# OUTPUT_HEADERS.net
KiCad netlist of a schematic drawn in Altium Designer
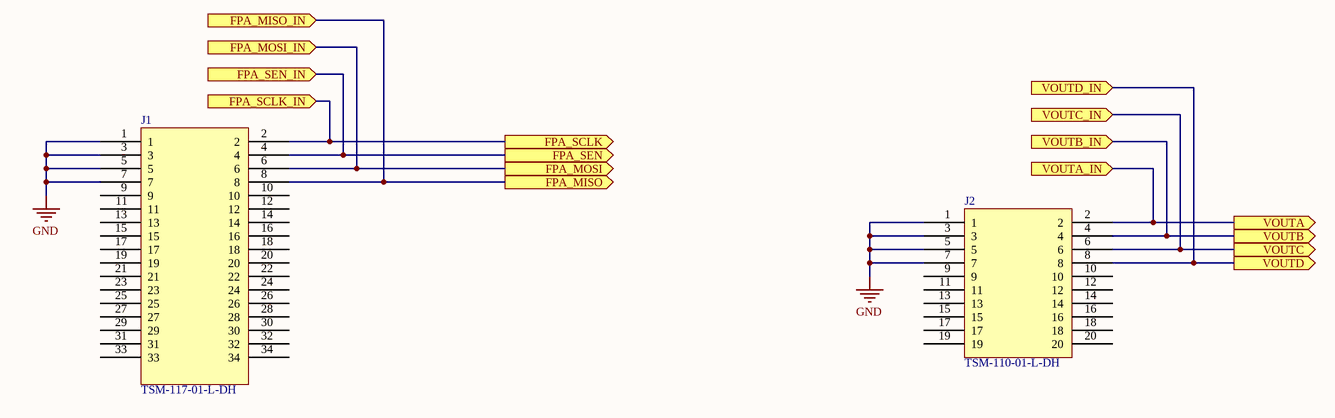
[diagram p0: OUTPUT HEADERS.SchDoc]

(export (version "E")
  (design (tool "Eeschema 10.0.6"))
  (components
    (comp (ref "J1")
      (value "TSM-117-01-L-DH")
      (footprint "HEADER_25.4MM_17x2_SMT_RA_TOP")
      (description "CONN HEADER 34POS .100\" DBL SMD")
      (fields (field (name "MANUFACTURER") "Samtec Inc"))
      (libsource (lib "Components") (part "TSM-117-01-L-DH"))
    )
    (comp (ref "J2")
      (value "TSM-110-01-L-DH")
      (footprint "HEADER_25.4MM_10x2_SMT_RA_TOP")
      (description "CONN HEADER 20POS .100\" DBL SMD")
      (fields (field (name "MANUFACTURER") "Samtec Inc"))
      (libsource (lib "Components") (part "TSM-110-01-L-DH"))
    )
  )
  (nets
    (net (code "1") (name "/FPA_MISO") (class "Default")
      (node (ref "J1") (pin "8") (pinfunction "8_8") (pintype "passive"))
    )
    (net (code "2") (name "/FPA_MOSI") (class "Default")
      (node (ref "J1") (pin "6") (pinfunction "6_6") (pintype "passive"))
    )
    (net (code "3") (name "/FPA_SCLK") (class "Default")
      (node (ref "J1") (pin "2") (pinfunction "2_2") (pintype "passive"))
    )
    (net (code "4") (name "/FPA_SEN") (class "Default")
      (node (ref "J1") (pin "4") (pinfunction "4_4") (pintype "passive"))
    )
    (net (code "5") (name "/VOUTA") (class "Default")
      (node (ref "J2") (pin "2") (pinfunction "2_2") (pintype "passive"))
    )
    (net (code "6") (name "/VOUTB") (class "Default")
      (node (ref "J2") (pin "4") (pinfunction "4_4") (pintype "passive"))
    )
    (net (code "7") (name "/VOUTC") (class "Default")
      (node (ref "J2") (pin "6") (pinfunction "6_6") (pintype "passive"))
    )
    (net (code "8") (name "/VOUTD") (class "Default")
      (node (ref "J2") (pin "8") (pinfunction "8_8") (pintype "passive"))
    )
    (net (code "9") (name "GND") (class "Default")
      (node (ref "J1") (pin "1") (pinfunction "1_1") (pintype "passive"))
      (node (ref "J1") (pin "3") (pinfunction "3_3") (pintype "passive"))
      (node (ref "J1") (pin "5") (pinfunction "5_5") (pintype "passive"))
      (node (ref "J1") (pin "7") (pinfunction "7_7") (pintype "passive"))
      (node (ref "J2") (pin "1") (pinfunction "1_1") (pintype "passive"))
      (node (ref "J2") (pin "3") (pinfunction "3_3") (pintype "passive"))
      (node (ref "J2") (pin "5") (pinfunction "5_5") (pintype "passive"))
      (node (ref "J2") (pin "7") (pinfunction "7_7") (pintype "passive"))
    )
    (net (code "10") (name "unconnected-(J1-Pad9)") (class "Default")
      (node (ref "J1") (pin "9") (pinfunction "9_9") (pintype "passive"))
    )
    (net (code "11") (name "unconnected-(J1-Pad10)") (class "Default")
      (node (ref "J1") (pin "10") (pinfunction "10_10") (pintype "passive"))
    )
    (net (code "12") (name "unconnected-(J1-Pad11)") (class "Default")
      (node (ref "J1") (pin "11") (pinfunction "11_11") (pintype "passive"))
    )
    (net (code "13") (name "unconnected-(J1-Pad12)") (class "Default")
      (node (ref "J1") (pin "12") (pinfunction "12_12") (pintype "passive"))
    )
    (net (code "14") (name "unconnected-(J1-Pad13)") (class "Default")
      (node (ref "J1") (pin "13") (pinfunction "13_13") (pintype "passive"))
    )
    (net (code "15") (name "unconnected-(J1-Pad14)") (class "Default")
      (node (ref "J1") (pin "14") (pinfunction "14_14") (pintype "passive"))
    )
    (net (code "16") (name "unconnected-(J1-Pad15)") (class "Default")
      (node (ref "J1") (pin "15") (pinfunction "15_15") (pintype "passive"))
    )
    (net (code "17") (name "unconnected-(J1-Pad16)") (class "Default")
      (node (ref "J1") (pin "16") (pinfunction "16_16") (pintype "passive"))
    )
    (net (code "18") (name "unconnected-(J1-Pad17)") (class "Default")
      (node (ref "J1") (pin "17") (pinfunction "17_17") (pintype "passive"))
    )
    (net (code "19") (name "unconnected-(J1-Pad18)") (class "Default")
      (node (ref "J1") (pin "18") (pinfunction "18_18") (pintype "passive"))
    )
    (net (code "20") (name "unconnected-(J1-Pad19)") (class "Default")
      (node (ref "J1") (pin "19") (pinfunction "19_19") (pintype "passive"))
    )
    (net (code "21") (name "unconnected-(J1-Pad20)") (class "Default")
      (node (ref "J1") (pin "20") (pinfunction "20_20") (pintype "passive"))
    )
    (net (code "22") (name "unconnected-(J1-Pad21)") (class "Default")
      (node (ref "J1") (pin "21") (pinfunction "21_21") (pintype "passive"))
    )
    (net (code "23") (name "unconnected-(J1-Pad22)") (class "Default")
      (node (ref "J1") (pin "22") (pinfunction "22_22") (pintype "passive"))
    )
    (net (code "24") (name "unconnected-(J1-Pad23)") (class "Default")
      (node (ref "J1") (pin "23") (pinfunction "23_23") (pintype "passive"))
    )
    (net (code "25") (name "unconnected-(J1-Pad24)") (class "Default")
      (node (ref "J1") (pin "24") (pinfunction "24_24") (pintype "passive"))
    )
    (net (code "26") (name "unconnected-(J1-Pad25)") (class "Default")
      (node (ref "J1") (pin "25") (pinfunction "25_25") (pintype "passive"))
    )
    (net (code "27") (name "unconnected-(J1-Pad26)") (class "Default")
      (node (ref "J1") (pin "26") (pinfunction "26_26") (pintype "passive"))
    )
    (net (code "28") (name "unconnected-(J1-Pad27)") (class "Default")
      (node (ref "J1") (pin "27") (pinfunction "27_27") (pintype "passive"))
    )
    (net (code "29") (name "unconnected-(J1-Pad28)") (class "Default")
      (node (ref "J1") (pin "28") (pinfunction "28_28") (pintype "passive"))
    )
    (net (code "30") (name "unconnected-(J1-Pad29)") (class "Default")
      (node (ref "J1") (pin "29") (pinfunction "29_29") (pintype "passive"))
    )
    (net (code "31") (name "unconnected-(J1-Pad30)") (class "Default")
      (node (ref "J1") (pin "30") (pinfunction "30_30") (pintype "passive"))
    )
    (net (code "32") (name "unconnected-(J1-Pad31)") (class "Default")
      (node (ref "J1") (pin "31") (pinfunction "31_31") (pintype "passive"))
    )
    (net (code "33") (name "unconnected-(J1-Pad32)") (class "Default")
      (node (ref "J1") (pin "32") (pinfunction "32_32") (pintype "passive"))
    )
    (net (code "34") (name "unconnected-(J1-Pad33)") (class "Default")
      (node (ref "J1") (pin "33") (pinfunction "33_33") (pintype "passive"))
    )
    (net (code "35") (name "unconnected-(J1-Pad34)") (class "Default")
      (node (ref "J1") (pin "34") (pinfunction "34_34") (pintype "passive"))
    )
    (net (code "36") (name "unconnected-(J2-Pad9)") (class "Default")
      (node (ref "J2") (pin "9") (pinfunction "9_9") (pintype "passive"))
    )
    (net (code "37") (name "unconnected-(J2-Pad10)") (class "Default")
      (node (ref "J2") (pin "10") (pinfunction "10_10") (pintype "passive"))
    )
    (net (code "38") (name "unconnected-(J2-Pad11)") (class "Default")
      (node (ref "J2") (pin "11") (pinfunction "11_11") (pintype "passive"))
    )
    (net (code "39") (name "unconnected-(J2-Pad12)") (class "Default")
      (node (ref "J2") (pin "12") (pinfunction "12_12") (pintype "passive"))
    )
    (net (code "40") (name "unconnected-(J2-Pad13)") (class "Default")
      (node (ref "J2") (pin "13") (pinfunction "13_13") (pintype "passive"))
    )
    (net (code "41") (name "unconnected-(J2-Pad14)") (class "Default")
      (node (ref "J2") (pin "14") (pinfunction "14_14") (pintype "passive"))
    )
    (net (code "42") (name "unconnected-(J2-Pad15)") (class "Default")
      (node (ref "J2") (pin "15") (pinfunction "15_15") (pintype "passive"))
    )
    (net (code "43") (name "unconnected-(J2-Pad16)") (class "Default")
      (node (ref "J2") (pin "16") (pinfunction "16_16") (pintype "passive"))
    )
    (net (code "44") (name "unconnected-(J2-Pad17)") (class "Default")
      (node (ref "J2") (pin "17") (pinfunction "17_17") (pintype "passive"))
    )
    (net (code "45") (name "unconnected-(J2-Pad18)") (class "Default")
      (node (ref "J2") (pin "18") (pinfunction "18_18") (pintype "passive"))
    )
    (net (code "46") (name "unconnected-(J2-Pad19)") (class "Default")
      (node (ref "J2") (pin "19") (pinfunction "19_19") (pintype "passive"))
    )
    (net (code "47") (name "unconnected-(J2-Pad20)") (class "Default")
      (node (ref "J2") (pin "20") (pinfunction "20_20") (pintype "passive"))
    )
  )
)
